# initial_circuit.net
KiCad netlist of a schematic drawn in Altium Designer
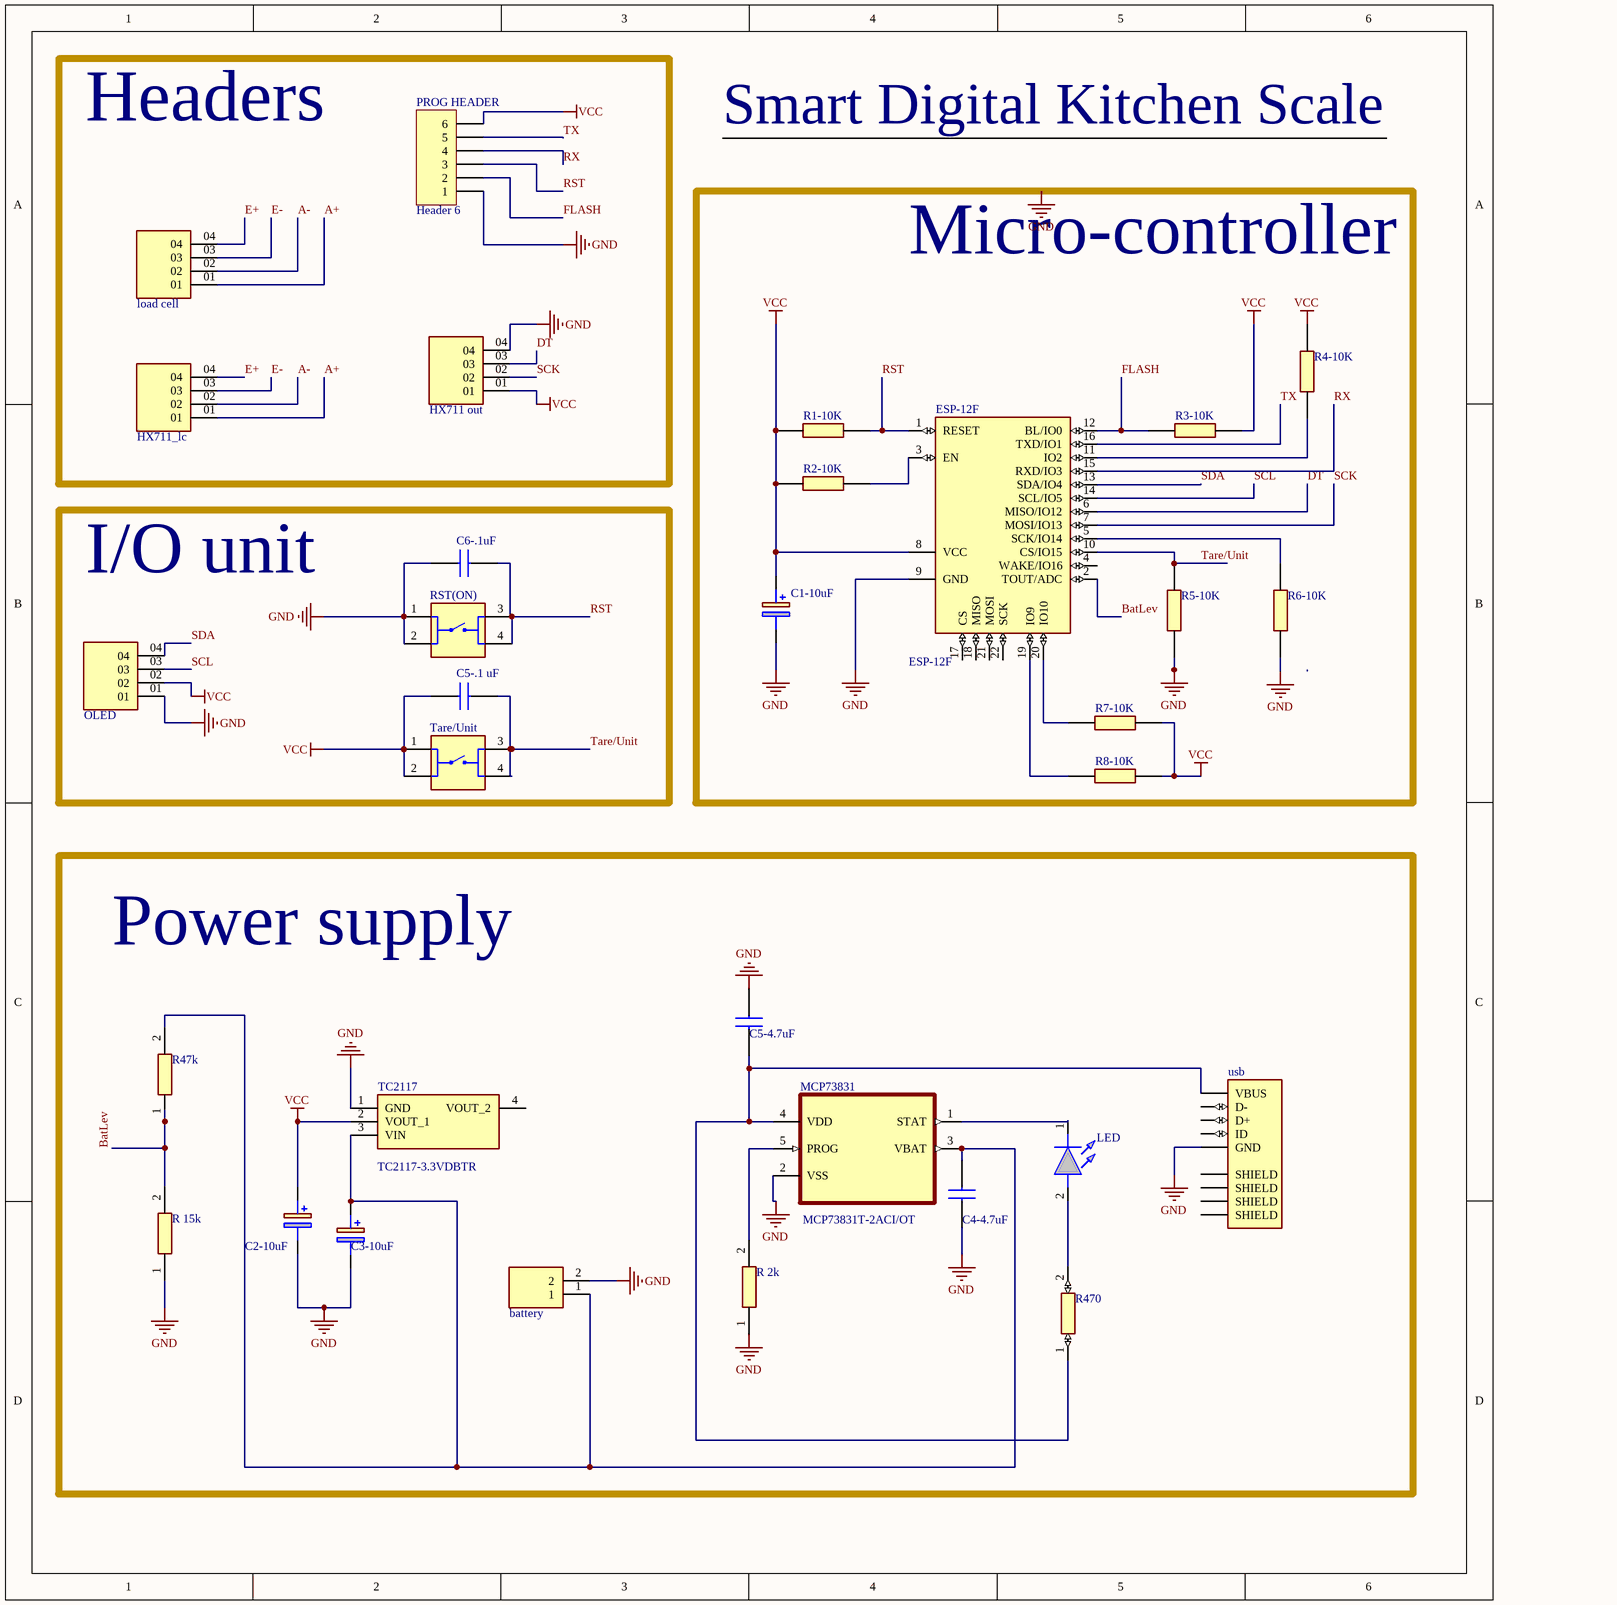
[diagram p0: initial circuit.SchDoc]

(export (version "E")
  (design (tool "Eeschema 10.0.6"))
  (components
    (comp (ref "battery")
      (value "B2B-XH-A(LF)(SN)")
      (footprint "JST_B2B-XH-A(LF)(SN)")
      (description "Connector Header Through Hole 2 position 0.098 (2.50mm)")
      (fields (field (name "MF") "JST Sales"))
      (libsource (lib "B2B-XH-A_LF__SN_") (part "B2B-XH-A(LF)(SN)"))
    )
    (comp (ref "C1-10uF")
      (value "865080340001")
      (footprint "CAPAE430X550N:CAPAE430X550N")
      (fields (field (name "MOUSER PART NUMBER") "710-865080340001"))
      (libsource (lib "865080340001") (part "865080340001"))
    )
    (comp (ref "C2-10uF")
      (value "865080340001")
      (footprint "CAPAE430X550N")
      (fields (field (name "MOUSER PART NUMBER") "710-865080340001"))
      (libsource (lib "865080340001") (part "865080340001"))
    )
    (comp (ref "C3-10uF")
      (value "865080340001")
      (footprint "CAPAE430X550N")
      (fields (field (name "MOUSER PART NUMBER") "710-865080340001"))
      (libsource (lib "865080340001") (part "865080340001"))
    )
    (comp (ref "C4-4.7uF")
      (value "885012107013")
      (footprint "CAPC2012X145N")
      (description "Multilayer Ceramic Capacitor 4.7uF 0805")
      (fields (field (name "MOUSER PART NUMBER") "710-885012107013"))
      (libsource (lib "885012107013") (part "885012107013"))
    )
    (comp (ref "C5-.1 uF")
      (value "C0805C104K5RAC7411")
      (footprint "CAPC2012X88N")
      (description "Cap Ceramic 0.1uF 50V X7R 10% Pad SMD 0805 125C T/R")
      (fields (field (name "MOUSER PART NUMBER") "80-C0805C104K5RACLR"))
      (libsource (lib "C0805C104K5RAC7411") (part "C0805C104K5RAC7411"))
    )
    (comp (ref "C5-4.7uF")
      (value "885012107013")
      (footprint "CAPC2012X145N:CAPC2012X145N")
      (description "Multilayer Ceramic Capacitor 4.7uF 0805")
      (fields (field (name "MOUSER PART NUMBER") "710-885012107013"))
      (libsource (lib "885012107013") (part "885012107013"))
    )
    (comp (ref "C6-.1uF")
      (value "C0805C104K5RAC7411")
      (footprint "CAPC2012X88N")
      (description "Cap Ceramic 0.1uF 50V X7R 10% Pad SMD 0805 125C T/R")
      (fields (field (name "MOUSER PART NUMBER") "80-C0805C104K5RACLR"))
      (libsource (lib "C0805C104K5RAC7411") (part "C0805C104K5RAC7411"))
    )
    (comp (ref "ESP-12F")
      (value "ESP-12F")
      (footprint "ESP-12F:ESP-12F")
      (description "WiFi Module")
      (fields (field (name "MF") "AI-Thinker"))
      (libsource (lib "ESP-12F") (part "ESP-12F"))
    )
    (comp (ref "HX711 out")
      (value "MTSW-104-XX-X-S-XXX")
      (footprint "female_header:SAMTEC_MTSW-104-XX-X-S-XXX")
      (fields (field (name "MF") "Samtec") (field (name "MP") "MTSW-104-12-F-S-850"))
      (libsource (lib "female_header") (part "MTSW-104-XX-X-S-XXX"))
    )
    (comp (ref "HX711_lc")
      (value "MTSW-104-XX-X-S-XXX")
      (footprint "SAMTEC_MTSW-104-XX-X-S-XXX")
      (fields (field (name "MF") "Samtec") (field (name "MP") "MTSW-104-12-F-S-850"))
      (libsource (lib "female_header") (part "MTSW-104-XX-X-S-XXX"))
    )
    (comp (ref "LED")
      (value "CLM3C-AKW-CUAVB253")
      (footprint "LEDM3020X140N")
      (description "Standard LEDs - SMD Amber LED Cree PLCC2 1 in 1 SMD LED CLM3C-RKW/AKW")
      (fields (field (name "MOUSER PART NUMBER") "941-CLM3CAKWCUAVB253"))
      (libsource (lib "CLM3C-AKW-CUAVB253") (part "CLM3C-AKW-CUAVB253"))
    )
    (comp (ref "load cell")
      (value "MTSW-104-XX-X-S-XXX")
      (footprint "SAMTEC_MTSW-104-XX-X-S-XXX")
      (fields (field (name "MF") "Samtec") (field (name "MP") "MTSW-104-12-F-S-850"))
      (libsource (lib "female_header") (part "MTSW-104-XX-X-S-XXX"))
    )
    (comp (ref "MCP73831")
      (value "MCP73831T-2ACI/OT")
      (footprint "SnapEDApcb:SOT95P280X145-5N")
      (description "Charger IC Lithium Ion/Polymer SOT-23-5")
      (fields (field (name "MP") "MCP73831T-5ACI/OT") (field (name "MF") "Microchip"))
      (libsource (lib "SnapEDAsch") (part "MCP73831T-5ACI/OT"))
    )
    (comp (ref "OLED")
      (value "MTSW-104-XX-X-S-XXX")
      (footprint "4 way pin header:SAMTEC_MTSW-104-XX-X-S-XXX")
      (fields (field (name "MF") "Samtec") (field (name "MP") "MTSW-104-12-F-S-850"))
      (libsource (lib "MTSW-104-XX-X-S-XXX") (part "MTSW-104-XX-X-S-XXX"))
    )
    (comp (ref "PROG HEADER")
      (value "Header 6")
      (footprint "HDR1X6")
      (description "Header, 6-Pin")
      (fields (field (name "PUBLISHER") "Altium Limited"))
      (libsource (lib "Miscellaneous Connectors") (part "Header 6"))
    )
    (comp (ref "R 2k")
      (value "CR0805-JW-202ELF")
      (footprint "SamacSys:RESC2012X60N")
      (description "Resistor")
      (fields (field (name "MOUSER PART NUMBER") "652-CR0805JW-202ELF"))
      (libsource (lib "*") (part "CR0805-JW-202ELF"))
    )
    (comp (ref "R 15k")
      (value "ERJ-6GEYJ153V")
      (footprint "SamacSys:RESC2012X70N")
      (description "Resistor")
      (fields (field (name "MOUSER PART NUMBER") "667-ERJ-6GEYJ153V"))
      (libsource (lib "*") (part "ERJ-6GEYJ153V"))
    )
    (comp (ref "R1-10K")
      (value "CRGCQ0805J10K")
      (footprint "RESC2013X65N")
      (description "TE CONNECTIVITY - CRGCQ0805J10K - RES, 10K, 5%, 0805, THICK FILM")
      (fields (field (name "MOUSER PART NUMBER") "279-CRGCQ0805J10K"))
      (libsource (lib "CRGCQ0805J10K") (part "CRGCQ0805J10K"))
    )
    (comp (ref "R2-10K")
      (value "CRGCQ0805J10K")
      (footprint "RESC2013X65N")
      (description "TE CONNECTIVITY - CRGCQ0805J10K - RES, 10K, 5%, 0805, THICK FILM")
      (fields (field (name "MOUSER PART NUMBER") "279-CRGCQ0805J10K"))
      (libsource (lib "CRGCQ0805J10K") (part "CRGCQ0805J10K"))
    )
    (comp (ref "R3-10K")
      (value "CRGCQ0805J10K")
      (footprint "RESC2013X65N")
      (description "TE CONNECTIVITY - CRGCQ0805J10K - RES, 10K, 5%, 0805, THICK FILM")
      (fields (field (name "MOUSER PART NUMBER") "279-CRGCQ0805J10K"))
      (libsource (lib "CRGCQ0805J10K") (part "CRGCQ0805J10K"))
    )
    (comp (ref "R4-10K")
      (value "CRGCQ0805J10K")
      (footprint "RESC2013X65N")
      (description "TE CONNECTIVITY - CRGCQ0805J10K - RES, 10K, 5%, 0805, THICK FILM")
      (fields (field (name "MOUSER PART NUMBER") "279-CRGCQ0805J10K"))
      (libsource (lib "") (part "CRGCQ0805J10K_1"))
    )
    (comp (ref "R5-10K")
      (value "CRGCQ0805J10K")
      (footprint "RESC2013X65N")
      (description "TE CONNECTIVITY - CRGCQ0805J10K - RES, 10K, 5%, 0805, THICK FILM")
      (fields (field (name "MOUSER PART NUMBER") "279-CRGCQ0805J10K"))
      (libsource (lib "") (part "CRGCQ0805J10K_1"))
    )
    (comp (ref "R6-10K")
      (value "CRGCQ0805J10K")
      (footprint "RESC2013X65N")
      (description "TE CONNECTIVITY - CRGCQ0805J10K - RES, 10K, 5%, 0805, THICK FILM")
      (fields (field (name "MOUSER PART NUMBER") "279-CRGCQ0805J10K"))
      (libsource (lib "") (part "CRGCQ0805J10K_1"))
    )
    (comp (ref "R7-10K")
      (value "CRGCQ0805J10K")
      (footprint "RESC2013X65N")
      (description "TE CONNECTIVITY - CRGCQ0805J10K - RES, 10K, 5%, 0805, THICK FILM")
      (fields (field (name "MOUSER PART NUMBER") "279-CRGCQ0805J10K"))
      (libsource (lib "CRGCQ0805J10K") (part "CRGCQ0805J10K"))
    )
    (comp (ref "R8-10K")
      (value "CRGCQ0805J10K")
      (footprint "RESC2013X65N")
      (description "TE CONNECTIVITY - CRGCQ0805J10K - RES, 10K, 5%, 0805, THICK FILM")
      (fields (field (name "MOUSER PART NUMBER") "279-CRGCQ0805J10K"))
      (libsource (lib "CRGCQ0805J10K") (part "CRGCQ0805J10K"))
    )
    (comp (ref "R47k")
      (value "CR0805-JW-473ELF")
      (footprint "SamacSys:RESC2012X60N")
      (description "Resistor")
      (fields (field (name "MOUSER PART NUMBER") "652-CR0805JW-473ELF"))
      (libsource (lib "*") (part "CR0805-JW-473ELF"))
    )
    (comp (ref "R470")
      (value "CRCW0805470RFKEAC")
      (footprint "SamacSys:RESC2012X60N")
      (description "Resistor")
      (fields (field (name "MOUSER PART NUMBER") "71-CRCW0805470RFKEAC"))
      (libsource (lib "*") (part "CRCW0805470RFKEAC"))
    )
    (comp (ref "RST(ON)")
      (value "1825910-2")
      (footprint "TE_1825910-2")
      (description "50 mA SPST Round Actuator 160 Gram Force Tactile Pushbutton Switch")
      (fields (field (name "MF") "TE Connectivity"))
      (libsource (lib "1825910-2") (part "1825910-2"))
    )
    (comp (ref "Tare/Unit")
      (value "1825910-2")
      (footprint "TE_1825910-2")
      (description "50 mA SPST Round Actuator 160 Gram Force Tactile Pushbutton Switch")
      (fields (field (name "MF") "TE Connectivity"))
      (libsource (lib "1825910-2") (part "1825910-2"))
    )
    (comp (ref "TC2117")
      (value "TC2117-3.3VDBTR")
      (footprint "SOT230P700X180-4N")
      (description "Microchip TC2117-3.3VDBTR, LDO Voltage Regulator, 800mA, 3.3 V +/-0.5%, 2.7  6 Vin, 3-Pin SOT-223")
      (fields (field (name "MOUSER PART NUMBER") "579-TC2117-3.3VDBTR"))
      (libsource (lib "TC2117-3.3VDBTR") (part "TC2117-3.3VDBTR"))
    )
    (comp (ref "usb")
      (value "USB3090-XX-X_REVE")
      (footprint "GCT_USB3090-XX-X_REVE:GCT_USB3090-XX-X_REVE")
      (description "Micro USB Receptacle, Type AB, SMT, R/A, Bottom Mount, w/out Peg, w/outer shell stakes")
      (libsource (lib "USB3090-XX-X_REVE") (part "USB3090-XX-X_REVE"))
    )
  )
  (nets
    (net (code "1") (name "/A+") (class "Default")
      (node (ref "HX711_lc") (pin "01") (pinfunction "01_01") (pintype "passive"))
      (node (ref "load cell") (pin "01") (pinfunction "01_01") (pintype "passive"))
    )
    (net (code "2") (name "/A-") (class "Default")
      (node (ref "HX711_lc") (pin "02") (pinfunction "02_02") (pintype "passive"))
      (node (ref "load cell") (pin "02") (pinfunction "02_02") (pintype "passive"))
    )
    (net (code "3") (name "/BatLev") (class "Default")
      (node (ref "ESP-12F") (pin "2") (pinfunction "TOUT/ADC_2") (pintype "bidirectional"))
      (node (ref "R 15k") (pin "2") (pinfunction "2_2") (pintype "passive"))
      (node (ref "R47k") (pin "1") (pinfunction "1_1") (pintype "passive"))
    )
    (net (code "4") (name "/DT") (class "Default")
      (node (ref "ESP-12F") (pin "6") (pinfunction "MISO/IO12_6") (pintype "bidirectional"))
      (node (ref "HX711 out") (pin "03") (pinfunction "03_03") (pintype "passive"))
    )
    (net (code "5") (name "/E+") (class "Default")
      (node (ref "HX711_lc") (pin "04") (pinfunction "04_04") (pintype "passive"))
      (node (ref "load cell") (pin "04") (pinfunction "04_04") (pintype "passive"))
    )
    (net (code "6") (name "/E-") (class "Default")
      (node (ref "HX711_lc") (pin "03") (pinfunction "03_03") (pintype "passive"))
      (node (ref "load cell") (pin "03") (pinfunction "03_03") (pintype "passive"))
    )
    (net (code "7") (name "/FLASH") (class "Default")
      (node (ref "ESP-12F") (pin "12") (pinfunction "BL/IO0_12") (pintype "bidirectional"))
      (node (ref "PROG HEADER") (pin "2") (pinfunction "2_2") (pintype "passive"))
      (node (ref "R3-10K") (pin "1") (pinfunction "1_1") (pintype "passive"))
    )
    (net (code "8") (name "/RST") (class "Default")
      (node (ref "C6-.1uF") (pin "2") (pinfunction "2_2") (pintype "passive"))
      (node (ref "ESP-12F") (pin "1") (pinfunction "RESET_1") (pintype "bidirectional"))
      (node (ref "PROG HEADER") (pin "3") (pinfunction "3_3") (pintype "passive"))
      (node (ref "R1-10K") (pin "2") (pinfunction "2_2") (pintype "passive"))
      (node (ref "RST(ON)") (pin "3") (pinfunction "3_3") (pintype "passive"))
      (node (ref "RST(ON)") (pin "4") (pinfunction "4_4") (pintype "passive"))
    )
    (net (code "9") (name "/RX") (class "Default")
      (node (ref "ESP-12F") (pin "15") (pinfunction "RXD/IO3_15") (pintype "bidirectional"))
      (node (ref "PROG HEADER") (pin "4") (pinfunction "4_4") (pintype "passive"))
    )
    (net (code "10") (name "/SCK") (class "Default")
      (node (ref "ESP-12F") (pin "7") (pinfunction "MOSI/IO13_7") (pintype "bidirectional"))
      (node (ref "HX711 out") (pin "02") (pinfunction "02_02") (pintype "passive"))
    )
    (net (code "11") (name "/SCL") (class "Default")
      (node (ref "ESP-12F") (pin "14") (pinfunction "SCL/IO5_14") (pintype "bidirectional"))
      (node (ref "OLED") (pin "03") (pinfunction "03_03") (pintype "passive"))
    )
    (net (code "12") (name "/SDA") (class "Default")
      (node (ref "ESP-12F") (pin "13") (pinfunction "SDA/IO4_13") (pintype "bidirectional"))
      (node (ref "OLED") (pin "04") (pinfunction "04_04") (pintype "passive"))
    )
    (net (code "13") (name "/TX") (class "Default")
      (node (ref "ESP-12F") (pin "16") (pinfunction "TXD/IO1_16") (pintype "bidirectional"))
      (node (ref "PROG HEADER") (pin "5") (pinfunction "5_5") (pintype "passive"))
    )
    (net (code "14") (name "/Tare{slash}Unit") (class "Default")
      (node (ref "C5-.1 uF") (pin "2") (pinfunction "2_2") (pintype "passive"))
      (node (ref "ESP-12F") (pin "10") (pinfunction "CS/IO15_10") (pintype "bidirectional"))
      (node (ref "R5-10K") (pin "1") (pinfunction "1_1") (pintype "passive"))
      (node (ref "Tare/Unit") (pin "3") (pinfunction "3_3") (pintype "passive"))
      (node (ref "Tare/Unit") (pin "4") (pinfunction "4_4") (pintype "passive"))
    )
    (net (code "15") (name "GND") (class "Default")
      (node (ref "C1-10uF") (pin "2") (pinfunction "-_2") (pintype "passive"))
      (node (ref "C2-10uF") (pin "2") (pinfunction "-_2") (pintype "passive"))
      (node (ref "C3-10uF") (pin "2") (pinfunction "-_2") (pintype "passive"))
      (node (ref "C4-4.7uF") (pin "1") (pinfunction "1_1") (pintype "passive"))
      (node (ref "C5-4.7uF") (pin "2") (pinfunction "2_2") (pintype "passive"))
      (node (ref "C6-.1uF") (pin "1") (pinfunction "1_1") (pintype "passive"))
      (node (ref "ESP-12F") (pin "9") (pinfunction "GND_9") (pintype "power_in"))
      (node (ref "HX711 out") (pin "04") (pinfunction "04_04") (pintype "passive"))
      (node (ref "MCP73831") (pin "2") (pinfunction "VSS_2") (pintype "power_in"))
      (node (ref "OLED") (pin "01") (pinfunction "01_01") (pintype "passive"))
      (node (ref "PROG HEADER") (pin "1") (pinfunction "1_1") (pintype "passive"))
      (node (ref "R 15k") (pin "1") (pinfunction "1_1") (pintype "passive"))
      (node (ref "R 2k") (pin "1") (pinfunction "1_1") (pintype "passive"))
      (node (ref "R5-10K") (pin "2") (pinfunction "2_2") (pintype "passive"))
      (node (ref "R6-10K") (pin "2") (pinfunction "2_2") (pintype "passive"))
      (node (ref "RST(ON)") (pin "1") (pinfunction "1_1") (pintype "passive"))
      (node (ref "RST(ON)") (pin "2") (pinfunction "2_2") (pintype "passive"))
      (node (ref "TC2117") (pin "1") (pinfunction "GND_1") (pintype "passive"))
      (node (ref "battery") (pin "2") (pinfunction "2_2") (pintype "passive"))
      (node (ref "usb") (pin "5") (pinfunction "GND_5") (pintype "power_in"))
    )
    (net (code "16") (name "Net-(C3-10uF-+)") (class "Default")
      (node (ref "C3-10uF") (pin "1") (pinfunction "+_1") (pintype "passive"))
      (node (ref "C4-4.7uF") (pin "2") (pinfunction "2_2") (pintype "passive"))
      (node (ref "MCP73831") (pin "3") (pinfunction "VBAT_3") (pintype "output"))
      (node (ref "R47k") (pin "2") (pinfunction "2_2") (pintype "passive"))
      (node (ref "TC2117") (pin "3") (pinfunction "VIN_3") (pintype "passive"))
      (node (ref "battery") (pin "1") (pinfunction "1_1") (pintype "passive"))
    )
    (net (code "17") (name "Net-(ESP-12F-EN)") (class "Default")
      (node (ref "ESP-12F") (pin "3") (pinfunction "EN_3") (pintype "bidirectional"))
      (node (ref "R2-10K") (pin "2") (pinfunction "2_2") (pintype "passive"))
    )
    (net (code "18") (name "Net-(ESP-12F-IO2)") (class "Default")
      (node (ref "ESP-12F") (pin "11") (pinfunction "IO2_11") (pintype "bidirectional"))
      (node (ref "R4-10K") (pin "2") (pinfunction "2_2") (pintype "passive"))
    )
    (net (code "19") (name "Net-(ESP-12F-IO9)") (class "Default")
      (node (ref "ESP-12F") (pin "19") (pinfunction "IO9_19") (pintype "bidirectional"))
      (node (ref "R8-10K") (pin "1") (pinfunction "1_1") (pintype "passive"))
    )
    (net (code "20") (name "Net-(ESP-12F-IO10)") (class "Default")
      (node (ref "ESP-12F") (pin "20") (pinfunction "IO10_20") (pintype "bidirectional"))
      (node (ref "R7-10K") (pin "1") (pinfunction "1_1") (pintype "passive"))
    )
    (net (code "21") (name "Net-(ESP-12F-SCK{slash}IO14)") (class "Default")
      (node (ref "ESP-12F") (pin "5") (pinfunction "SCK/IO14_5") (pintype "bidirectional"))
      (node (ref "R6-10K") (pin "1") (pinfunction "1_1") (pintype "passive"))
    )
    (net (code "22") (name "Net-(LED-A)") (class "Default")
      (node (ref "LED") (pin "2") (pinfunction "A_2") (pintype "passive"))
      (node (ref "R470") (pin "2") (pinfunction "2_2") (pintype "bidirectional"))
    )
    (net (code "23") (name "Net-(LED-K)") (class "Default")
      (node (ref "LED") (pin "1") (pinfunction "K_1") (pintype "passive"))
      (node (ref "MCP73831") (pin "1") (pinfunction "STAT_1") (pintype "output"))
    )
    (net (code "24") (name "Net-(MCP73831-PROG)") (class "Default")
      (node (ref "MCP73831") (pin "5") (pinfunction "PROG_5") (pintype "input"))
      (node (ref "R 2k") (pin "2") (pinfunction "2_2") (pintype "passive"))
    )
    (net (code "25") (name "Net-(MCP73831-VDD)") (class "Default")
      (node (ref "C5-4.7uF") (pin "1") (pinfunction "1_1") (pintype "passive"))
      (node (ref "MCP73831") (pin "4") (pinfunction "VDD_4") (pintype "power_in"))
      (node (ref "R470") (pin "1") (pinfunction "1_1") (pintype "bidirectional"))
      (node (ref "usb") (pin "1") (pinfunction "VBUS_1") (pintype "power_in"))
    )
    (net (code "26") (name "VCC") (class "Default")
      (node (ref "C1-10uF") (pin "1") (pinfunction "+_1") (pintype "passive"))
      (node (ref "C2-10uF") (pin "1") (pinfunction "+_1") (pintype "passive"))
      (node (ref "C5-.1 uF") (pin "1") (pinfunction "1_1") (pintype "passive"))
      (node (ref "ESP-12F") (pin "8") (pinfunction "VCC_8") (pintype "power_in"))
      (node (ref "HX711 out") (pin "01") (pinfunction "01_01") (pintype "passive"))
      (node (ref "OLED") (pin "02") (pinfunction "02_02") (pintype "passive"))
      (node (ref "PROG HEADER") (pin "6") (pinfunction "6_6") (pintype "passive"))
      (node (ref "R1-10K") (pin "1") (pinfunction "1_1") (pintype "passive"))
      (node (ref "R2-10K") (pin "1") (pinfunction "1_1") (pintype "passive"))
      (node (ref "R3-10K") (pin "2") (pinfunction "2_2") (pintype "passive"))
      (node (ref "R4-10K") (pin "1") (pinfunction "1_1") (pintype "passive"))
      (node (ref "R7-10K") (pin "2") (pinfunction "2_2") (pintype "passive"))
      (node (ref "R8-10K") (pin "2") (pinfunction "2_2") (pintype "passive"))
      (node (ref "TC2117") (pin "2") (pinfunction "VOUT_1_2") (pintype "passive"))
      (node (ref "Tare/Unit") (pin "1") (pinfunction "1_1") (pintype "passive"))
      (node (ref "Tare/Unit") (pin "2") (pinfunction "2_2") (pintype "passive"))
    )
    (net (code "27") (name "unconnected-(ESP-12F-CS-Pad17)") (class "Default")
      (node (ref "ESP-12F") (pin "17") (pinfunction "CS_17") (pintype "bidirectional"))
    )
    (net (code "28") (name "unconnected-(ESP-12F-MISO-Pad18)") (class "Default")
      (node (ref "ESP-12F") (pin "18") (pinfunction "MISO_18") (pintype "bidirectional"))
    )
    (net (code "29") (name "unconnected-(ESP-12F-MOSI-Pad21)") (class "Default")
      (node (ref "ESP-12F") (pin "21") (pinfunction "MOSI_21") (pintype "bidirectional"))
    )
    (net (code "30") (name "unconnected-(ESP-12F-SCK-Pad22)") (class "Default")
      (node (ref "ESP-12F") (pin "22") (pinfunction "SCK_22") (pintype "bidirectional"))
    )
    (net (code "31") (name "unconnected-(ESP-12F-WAKE{slash}IO16-Pad4)") (class "Default")
      (node (ref "ESP-12F") (pin "4") (pinfunction "WAKE/IO16_4") (pintype "bidirectional"))
    )
    (net (code "32") (name "unconnected-(TC2117-VOUT_2-Pad4)") (class "Default")
      (node (ref "TC2117") (pin "4") (pinfunction "VOUT_2_4") (pintype "passive"))
    )
    (net (code "33") (name "unconnected-(usb-D+-Pad3)") (class "Default")
      (node (ref "usb") (pin "3") (pinfunction "D+_3") (pintype "bidirectional"))
    )
    (net (code "34") (name "unconnected-(usb-D--Pad2)") (class "Default")
      (node (ref "usb") (pin "2") (pinfunction "D-_2") (pintype "bidirectional"))
    )
    (net (code "35") (name "unconnected-(usb-ID-Pad4)") (class "Default")
      (node (ref "usb") (pin "4") (pinfunction "ID_4") (pintype "bidirectional"))
    )
    (net (code "36") (name "unconnected-(usb-SHIELD-Pad6)") (class "Default")
      (node (ref "usb") (pin "6") (pinfunction "SHIELD_6") (pintype "power_in"))
    )
    (net (code "37") (name "unconnected-(usb-SHIELD-Pad7)") (class "Default")
      (node (ref "usb") (pin "7") (pinfunction "SHIELD_7") (pintype "power_in"))
    )
    (net (code "38") (name "unconnected-(usb-SHIELD-Pad8)") (class "Default")
      (node (ref "usb") (pin "8") (pinfunction "SHIELD_8") (pintype "power_in"))
    )
    (net (code "39") (name "unconnected-(usb-SHIELD-Pad9)") (class "Default")
      (node (ref "usb") (pin "9") (pinfunction "SHIELD_9") (pintype "power_in"))
    )
  )
)
